# line_kick.net
KiCad netlist of a schematic drawn in EAGLE
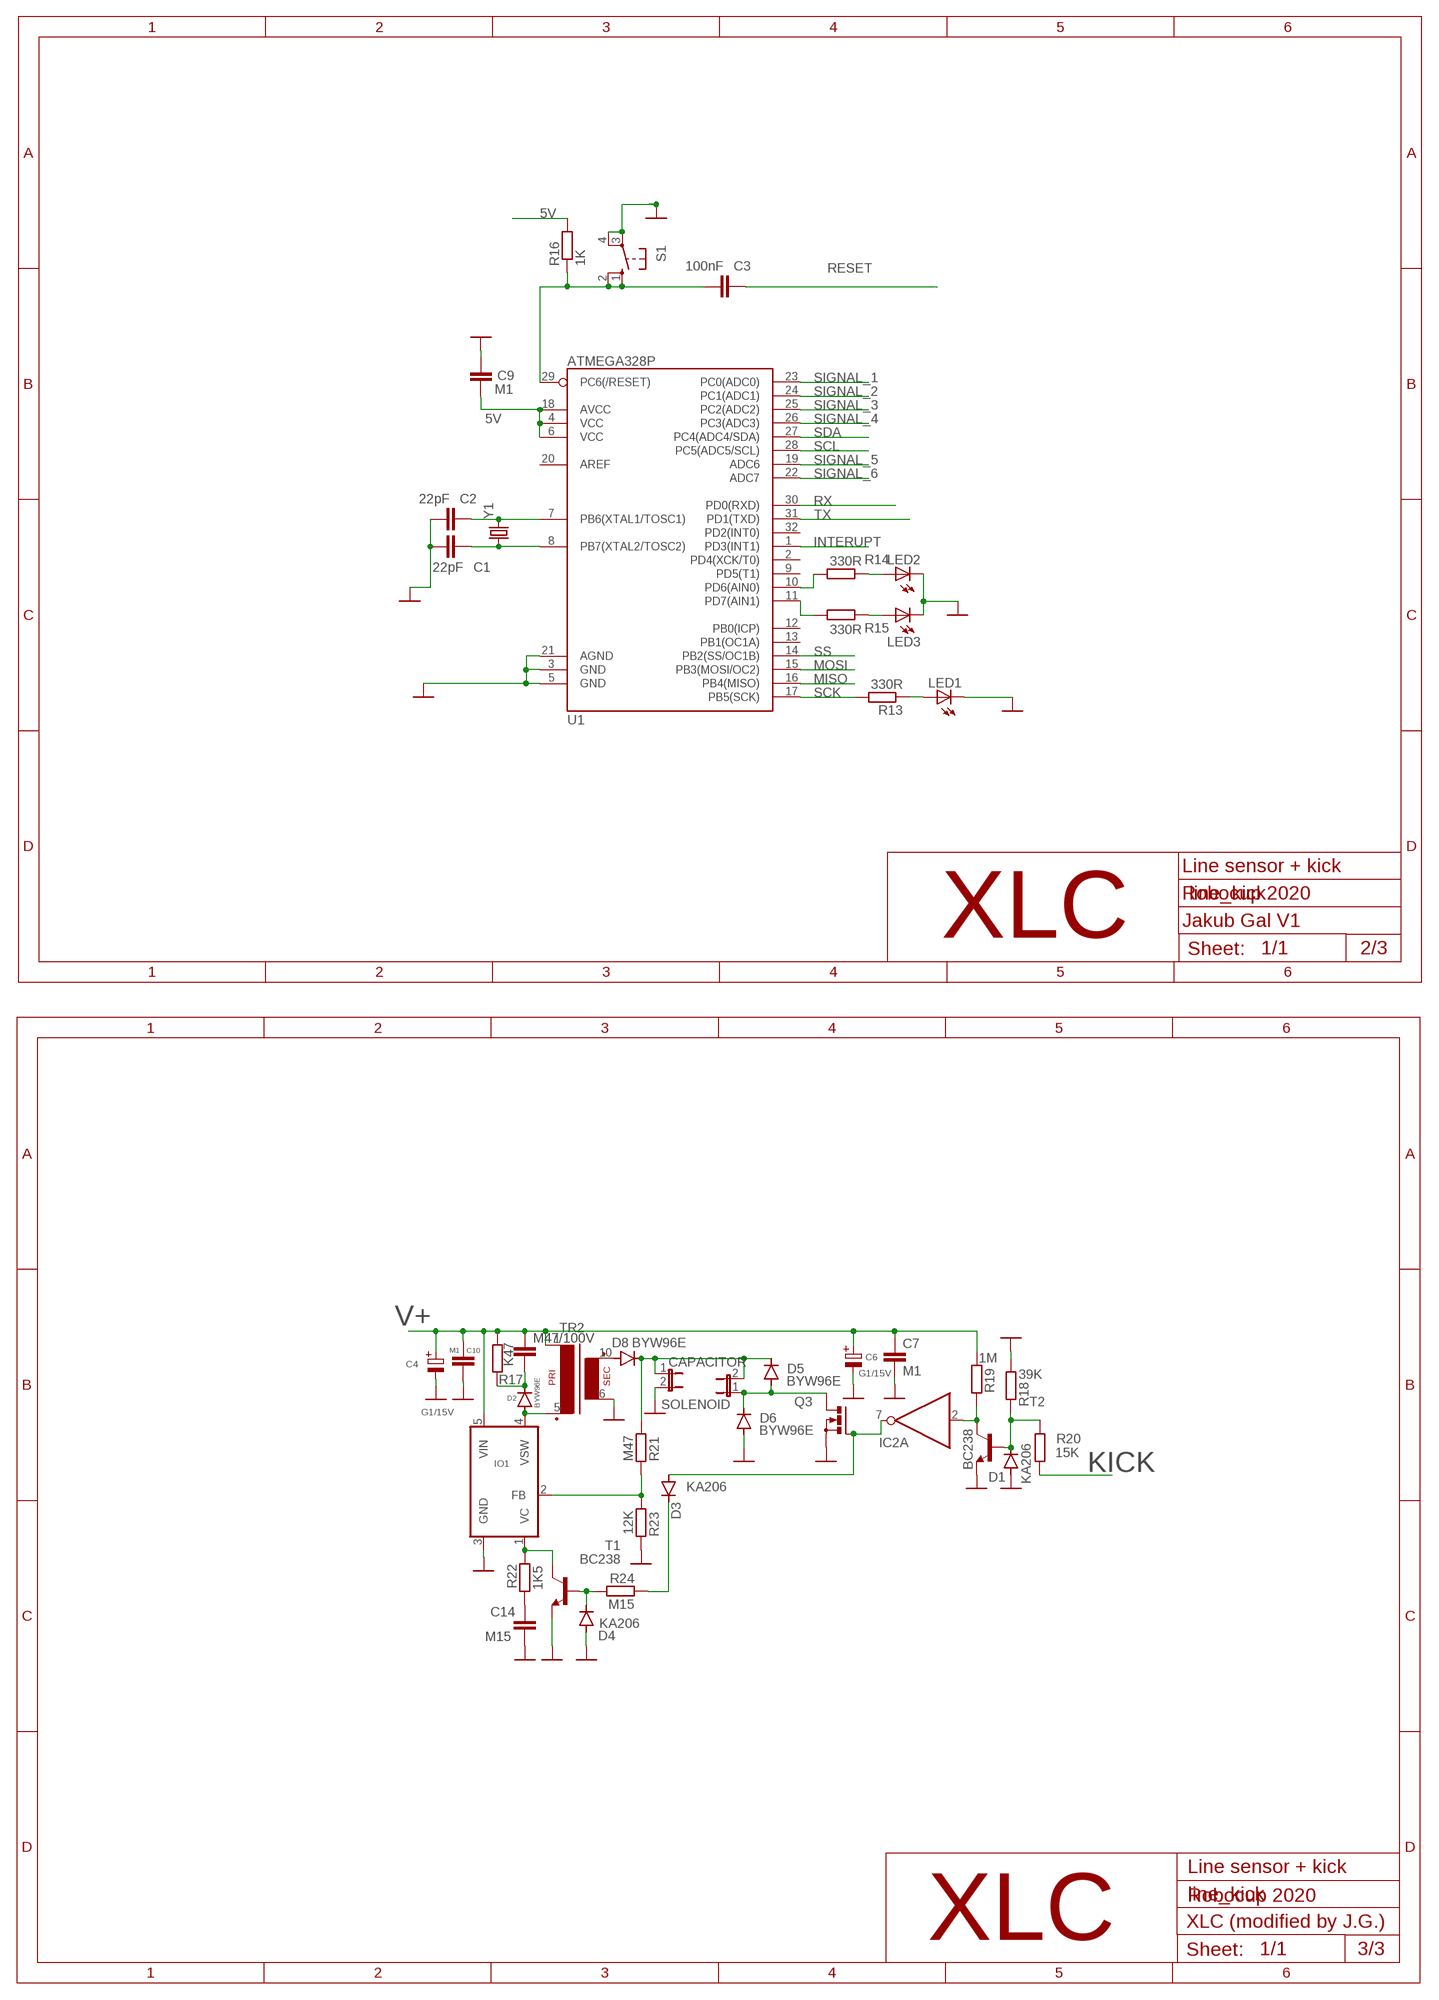
[diagram p0: schematic, sheet 1, part 1 of 2]
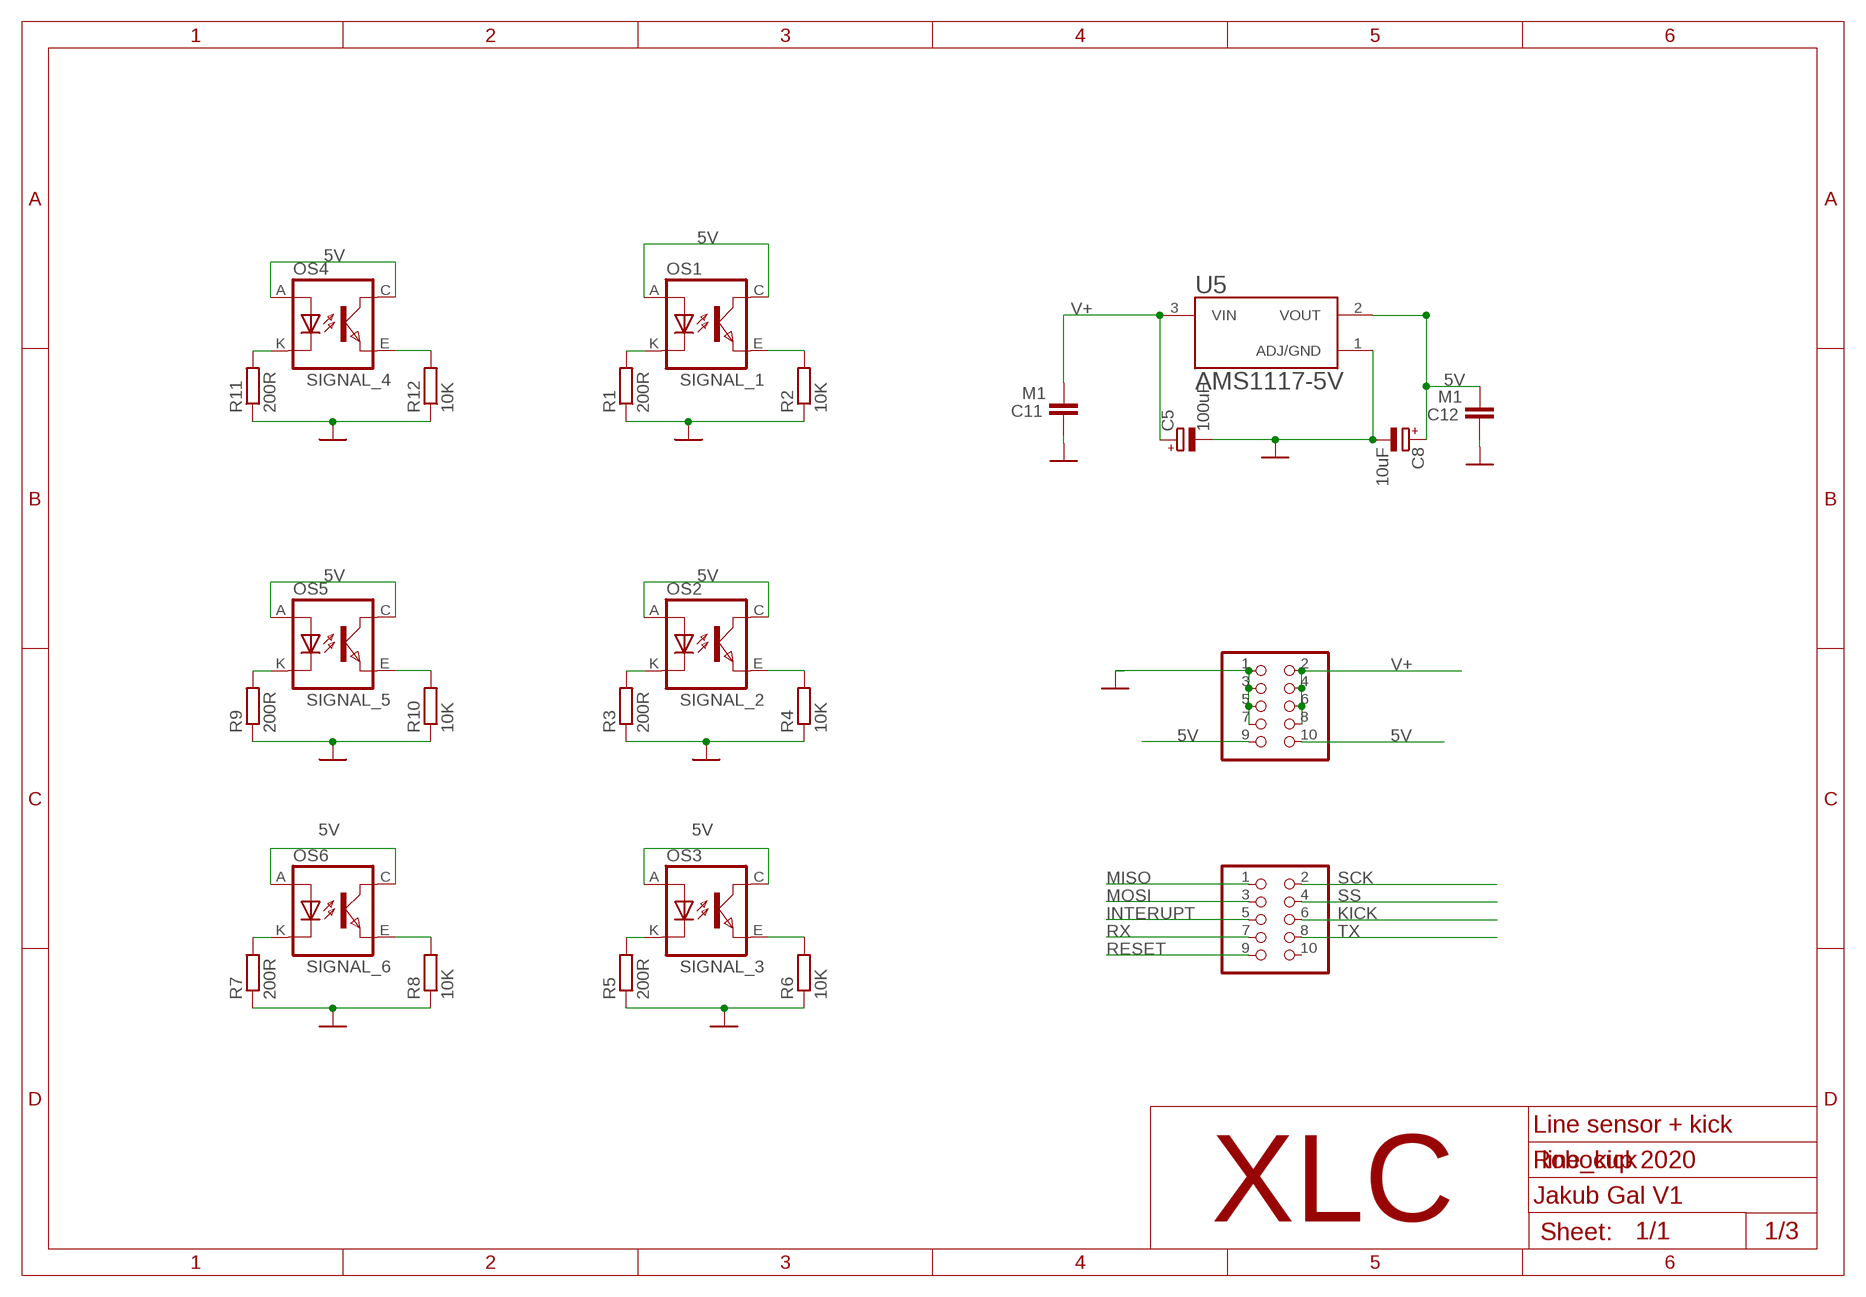
[diagram p1: schematic, sheet 1, part 2 of 2]

(export (version "E")
  (design (tool "Eeschema 10.0.6"))
  (components
    (comp (ref "C1")
      (value "22pF")
      (footprint "eagle-import:C0603")
      (libsource (lib "eagle-import") (part "C-EUC0603"))
    )
    (comp (ref "C2")
      (value "22pF")
      (footprint "eagle-import:C0603")
      (libsource (lib "eagle-import") (part "C-EUC0603"))
    )
    (comp (ref "C3")
      (value "100nF")
      (footprint "eagle-import:C0603")
      (libsource (lib "eagle-import") (part "C-EUC0603"))
    )
    (comp (ref "C4")
      (value "G1/15V")
      (footprint "eagle-import:E-2,5_7-RAD")
      (libsource (lib "eagle-import") (part "KOND-ELEKT-2,5/7"))
    )
    (comp (ref "C5")
      (value "100uF")
      (footprint "eagle-import:UD-6,3X7,7_NICHICON")
      (libsource (lib "eagle-import") (part "CPOL-EUUD-6,3X7,7"))
    )
    (comp (ref "C6")
      (value "G1/15V")
      (footprint "eagle-import:E-2,5_7-RAD")
      (libsource (lib "eagle-import") (part "KOND-ELEKT-2,5/7"))
    )
    (comp (ref "C7")
      (value "M1")
      (footprint "eagle-import:C0805K")
      (libsource (lib "eagle-import") (part "resistor_348_C-EUC0805K"))
    )
    (comp (ref "C8")
      (value "10uF")
      (footprint "eagle-import:UD-4X5,8_NICHICON")
      (libsource (lib "eagle-import") (part "CPOL-EUUD-4X5,8"))
    )
    (comp (ref "C9")
      (value "M1")
      (footprint "eagle-import:C0603")
      (libsource (lib "eagle-import") (part "C-EUC0603"))
    )
    (comp (ref "C10")
      (value "M1")
      (footprint "eagle-import:C0805K")
      (libsource (lib "eagle-import") (part "resistor_348_C-EUC0805K"))
    )
    (comp (ref "C11")
      (value "M1")
      (footprint "eagle-import:C0603")
      (libsource (lib "eagle-import") (part "C-EUC0603"))
    )
    (comp (ref "C12")
      (value "M1")
      (footprint "eagle-import:C0603")
      (libsource (lib "eagle-import") (part "C-EUC0603"))
    )
    (comp (ref "C14")
      (value "M15")
      (footprint "eagle-import:C0805K")
      (libsource (lib "eagle-import") (part "resistor_348_C-EUC0805K"))
    )
    (comp (ref "CAPACITOR")
      (value "JP1E")
      (footprint "eagle-import:JP1")
      (libsource (lib "eagle-import") (part "JP1E"))
    )
    (comp (ref "D1")
      (value "KA206")
      (footprint "eagle-import:D-7.5")
      (libsource (lib "eagle-import") (part "DIODE-D-7.5"))
    )
    (comp (ref "D2")
      (value "BYW96E")
      (footprint "eagle-import:SOD64-10")
      (libsource (lib "eagle-import") (part "BYW96"))
    )
    (comp (ref "D3")
      (value "KA206")
      (footprint "eagle-import:D-7.5")
      (libsource (lib "eagle-import") (part "DIODE-D-7.5"))
    )
    (comp (ref "D4")
      (value "KA206")
      (footprint "eagle-import:D-7.5")
      (libsource (lib "eagle-import") (part "DIODE-D-7.5"))
    )
    (comp (ref "D5")
      (value "BYW96E")
      (footprint "eagle-import:SOD64-10")
      (libsource (lib "eagle-import") (part "BYW96"))
    )
    (comp (ref "D6")
      (value "BYW96E")
      (footprint "eagle-import:SOD64-10")
      (libsource (lib "eagle-import") (part "BYW96"))
    )
    (comp (ref "D8")
      (value "BYW96E")
      (footprint "eagle-import:SOD64-10")
      (libsource (lib "eagle-import") (part "BYW96"))
    )
    (comp (ref "IC2")
      (value "MIC4423BM")
      (footprint "eagle-import:SO08")
      (libsource (lib "eagle-import") (part "MIC4423BM"))
    )
    (comp (ref "IO1")
      (value "LT1071V")
      (footprint "eagle-import:TO220-5P")
      (libsource (lib "eagle-import") (part "LT1071V"))
    )
    (comp (ref "JP2")
      (value "PINHD-2X5")
      (footprint "eagle-import:2X05")
      (libsource (lib "eagle-import") (part "PINHD-2X5"))
    )
    (comp (ref "JP3")
      (value "PINHD-2X5")
      (footprint "eagle-import:2X05")
      (libsource (lib "eagle-import") (part "PINHD-2X5"))
    )
    (comp (ref "LED1")
      (value "LEDCHIPLED_0603")
      (footprint "eagle-import:CHIPLED_0603")
      (libsource (lib "eagle-import") (part "LEDCHIPLED_0603"))
    )
    (comp (ref "LED2")
      (value "LEDCHIPLED_0603")
      (footprint "eagle-import:CHIPLED_0603")
      (libsource (lib "eagle-import") (part "LEDCHIPLED_0603"))
    )
    (comp (ref "LED3")
      (value "LEDCHIPLED_0603")
      (footprint "eagle-import:CHIPLED_0603")
      (libsource (lib "eagle-import") (part "LEDCHIPLED_0603"))
    )
    (comp (ref "M47/100V")
      (value "C-EUC0805K")
      (footprint "eagle-import:C0805K")
      (libsource (lib "eagle-import") (part "resistor_348_C-EUC0805K"))
    )
    (comp (ref "OS1")
      (value "TCRT5000")
      (footprint "eagle-import:TCRT5000")
      (libsource (lib "eagle-import") (part "TCRT5000"))
    )
    (comp (ref "OS2")
      (value "TCRT5000")
      (footprint "eagle-import:TCRT5000")
      (libsource (lib "eagle-import") (part "TCRT5000"))
    )
    (comp (ref "OS3")
      (value "TCRT5000")
      (footprint "eagle-import:TCRT5000")
      (libsource (lib "eagle-import") (part "TCRT5000"))
    )
    (comp (ref "OS4")
      (value "TCRT5000")
      (footprint "eagle-import:TCRT5000")
      (fields (field (name "SPICEPREFIX") "O"))
      (libsource (lib "eagle-import") (part "TCRT5000"))
    )
    (comp (ref "OS5")
      (value "TCRT5000")
      (footprint "eagle-import:TCRT5000")
      (libsource (lib "eagle-import") (part "TCRT5000"))
    )
    (comp (ref "OS6")
      (value "TCRT5000")
      (footprint "eagle-import:TCRT5000")
      (fields (field (name "SPICEPREFIX") "O"))
      (libsource (lib "eagle-import") (part "TCRT5000"))
    )
    (comp (ref "Q3")
      (value "PMOSFET_NTO220BV")
      (footprint "eagle-import:TO220BV")
      (libsource (lib "eagle-import") (part "PMOSFET_NTO220BV"))
    )
    (comp (ref "R1")
      (value "200R")
      (footprint "eagle-import:R0603")
      (libsource (lib "eagle-import") (part "R-EU_R0603"))
    )
    (comp (ref "R2")
      (value "10K")
      (footprint "eagle-import:R0603")
      (libsource (lib "eagle-import") (part "R-EU_R0603"))
    )
    (comp (ref "R3")
      (value "200R")
      (footprint "eagle-import:R0603")
      (libsource (lib "eagle-import") (part "R-EU_R0603"))
    )
    (comp (ref "R4")
      (value "10K")
      (footprint "eagle-import:R0603")
      (libsource (lib "eagle-import") (part "R-EU_R0603"))
    )
    (comp (ref "R5")
      (value "200R")
      (footprint "eagle-import:R0603")
      (libsource (lib "eagle-import") (part "R-EU_R0603"))
    )
    (comp (ref "R6")
      (value "10K")
      (footprint "eagle-import:R0603")
      (libsource (lib "eagle-import") (part "R-EU_R0603"))
    )
    (comp (ref "R7")
      (value "200R")
      (footprint "eagle-import:R0603")
      (libsource (lib "eagle-import") (part "R-EU_R0603"))
    )
    (comp (ref "R8")
      (value "10K")
      (footprint "eagle-import:R0603")
      (libsource (lib "eagle-import") (part "R-EU_R0603"))
    )
    (comp (ref "R9")
      (value "200R")
      (footprint "eagle-import:R0603")
      (libsource (lib "eagle-import") (part "R-EU_R0603"))
    )
    (comp (ref "R10")
      (value "10K")
      (footprint "eagle-import:R0603")
      (libsource (lib "eagle-import") (part "R-EU_R0603"))
    )
    (comp (ref "R11")
      (value "200R")
      (footprint "eagle-import:R0603")
      (libsource (lib "eagle-import") (part "R-EU_R0603"))
    )
    (comp (ref "R12")
      (value "10K")
      (footprint "eagle-import:R0603")
      (libsource (lib "eagle-import") (part "R-EU_R0603"))
    )
    (comp (ref "R13")
      (value "330R")
      (footprint "eagle-import:R0603")
      (libsource (lib "eagle-import") (part "R-EU_R0603"))
    )
    (comp (ref "R14")
      (value "330R")
      (footprint "eagle-import:R0603")
      (libsource (lib "eagle-import") (part "R-EU_R0603"))
    )
    (comp (ref "R15")
      (value "330R")
      (footprint "eagle-import:R0603")
      (libsource (lib "eagle-import") (part "R-EU_R0603"))
    )
    (comp (ref "R16")
      (value "1K")
      (footprint "eagle-import:R0603")
      (libsource (lib "eagle-import") (part "R-EU_R0603"))
    )
    (comp (ref "R17")
      (value "K47")
      (footprint "eagle-import:R0603")
      (libsource (lib "eagle-import") (part "resistor_348_R-EU_R0603"))
    )
    (comp (ref "R18")
      (value "39K")
      (footprint "eagle-import:R0603")
      (libsource (lib "eagle-import") (part "resistor_348_R-EU_R0603"))
    )
    (comp (ref "R19")
      (value "1M")
      (footprint "eagle-import:R0603")
      (libsource (lib "eagle-import") (part "resistor_348_R-EU_R0603"))
    )
    (comp (ref "R20")
      (value "15K")
      (footprint "eagle-import:R0603")
      (libsource (lib "eagle-import") (part "resistor_348_R-EU_R0603"))
    )
    (comp (ref "R21")
      (value "M47")
      (footprint "eagle-import:R0603")
      (libsource (lib "eagle-import") (part "resistor_348_R-EU_R0603"))
    )
    (comp (ref "R22")
      (value "1K5")
      (footprint "eagle-import:R0603")
      (libsource (lib "eagle-import") (part "resistor_348_R-EU_R0603"))
    )
    (comp (ref "R23")
      (value "12K")
      (footprint "eagle-import:R0603")
      (libsource (lib "eagle-import") (part "resistor_348_R-EU_R0603"))
    )
    (comp (ref "R24")
      (value "M15")
      (footprint "eagle-import:R0603")
      (libsource (lib "eagle-import") (part "resistor_348_R-EU_R0603"))
    )
    (comp (ref "S1")
      (value "10-XX")
      (footprint "eagle-import:B3F-10XX")
      (fields (field (name "MPN") "B3F-1000"))
      (libsource (lib "eagle-import") (part "10-XX"))
    )
    (comp (ref "SOLENOID")
      (value "JP1E")
      (footprint "eagle-import:JP1")
      (libsource (lib "eagle-import") (part "JP1E"))
    )
    (comp (ref "T1")
      (value "BC238")
      (footprint "eagle-import:TO92")
      (libsource (lib "eagle-import") (part "BC238"))
    )
    (comp (ref "T2")
      (value "BC238")
      (footprint "eagle-import:TO92")
      (libsource (lib "eagle-import") (part "BC238"))
    )
    (comp (ref "TR2")
      (value "TRAFO-E10-R\"\"")
      (footprint "eagle-import:TRAFO-EE17X20")
      (libsource (lib "eagle-import") (part "TRAFO-E10-R{dblquote}{dblquote}"))
    )
    (comp (ref "U1")
      (value "ATMEGA328P")
      (footprint "eagle-import:TQFP32-08")
      (libsource (lib "eagle-import") (part "ATMEGA328_SMT"))
    )
    (comp (ref "U5")
      (value "AMS1117-5V")
      (footprint "eagle-import:SOT229P700X180-4N")
      (fields (field (name "MF") "Advanced Monolithic Systems") (field (name "MP") "AMS1117-3.3"))
      (libsource (lib "eagle-import") (part "AMS1117-3.3"))
    )
    (comp (ref "Y1")
      (value "CRYSTALHC49US")
      (footprint "eagle-import:HC49US")
      (libsource (lib "eagle-import") (part "CRYSTALHC49US"))
    )
  )
  (nets
    (net (code "1") (name "/5V") (class "Default")
      (node (ref "C12") (pin "1") (pinfunction "1_1") (pintype "passive"))
      (node (ref "C8") (pin "+") (pinfunction "+_+") (pintype "passive"))
      (node (ref "C9") (pin "1") (pinfunction "1_1") (pintype "passive"))
      (node (ref "JP3") (pin "10") (pinfunction "10_10") (pintype "passive"))
      (node (ref "JP3") (pin "9") (pinfunction "9_9") (pintype "passive"))
      (node (ref "OS1") (pin "A") (pinfunction "ANODE_A") (pintype "passive"))
      (node (ref "OS1") (pin "C") (pinfunction "COLLECTOR_C") (pintype "passive"))
      (node (ref "OS2") (pin "A") (pinfunction "ANODE_A") (pintype "passive"))
      (node (ref "OS2") (pin "C") (pinfunction "COLLECTOR_C") (pintype "passive"))
      (node (ref "OS3") (pin "A") (pinfunction "ANODE_A") (pintype "passive"))
      (node (ref "OS3") (pin "C") (pinfunction "COLLECTOR_C") (pintype "passive"))
      (node (ref "OS4") (pin "A") (pinfunction "ANODE_A") (pintype "passive"))
      (node (ref "OS4") (pin "C") (pinfunction "COLLECTOR_C") (pintype "passive"))
      (node (ref "OS5") (pin "A") (pinfunction "ANODE_A") (pintype "passive"))
      (node (ref "OS5") (pin "C") (pinfunction "COLLECTOR_C") (pintype "passive"))
      (node (ref "OS6") (pin "A") (pinfunction "ANODE_A") (pintype "passive"))
      (node (ref "OS6") (pin "C") (pinfunction "COLLECTOR_C") (pintype "passive"))
      (node (ref "R16") (pin "2") (pinfunction "2_2") (pintype "passive"))
      (node (ref "U1") (pin "18") (pinfunction "AVCC_18") (pintype "bidirectional"))
      (node (ref "U1") (pin "4") (pinfunction "VCC_4") (pintype "bidirectional"))
      (node (ref "U1") (pin "6") (pinfunction "VCC_6") (pintype "bidirectional"))
      (node (ref "U5") (pin "2") (pinfunction "VOUT_2") (pintype "output"))
    )
    (net (code "2") (name "/INTERUPT") (class "Default")
      (node (ref "JP2") (pin "5") (pinfunction "5_5") (pintype "passive"))
      (node (ref "U1") (pin "1") (pinfunction "PD3(INT1)_1") (pintype "bidirectional"))
    )
    (net (code "3") (name "/KICK") (class "Default")
      (node (ref "JP2") (pin "6") (pinfunction "6_6") (pintype "passive"))
      (node (ref "R20") (pin "1") (pinfunction "1_1") (pintype "passive"))
    )
    (net (code "4") (name "/MISO") (class "Default")
      (node (ref "JP2") (pin "1") (pinfunction "1_1") (pintype "passive"))
      (node (ref "U1") (pin "16") (pinfunction "PB4(MISO)_16") (pintype "bidirectional"))
    )
    (net (code "5") (name "/MOSI") (class "Default")
      (node (ref "JP2") (pin "3") (pinfunction "3_3") (pintype "passive"))
      (node (ref "U1") (pin "15") (pinfunction "PB3(MOSI/OC2)_15") (pintype "bidirectional"))
    )
    (net (code "6") (name "/RESET") (class "Default")
      (node (ref "C3") (pin "2") (pinfunction "2_2") (pintype "passive"))
      (node (ref "JP2") (pin "9") (pinfunction "9_9") (pintype "passive"))
    )
    (net (code "7") (name "/RX") (class "Default")
      (node (ref "JP2") (pin "7") (pinfunction "7_7") (pintype "passive"))
      (node (ref "U1") (pin "30") (pinfunction "PD0(RXD)_30") (pintype "bidirectional"))
    )
    (net (code "8") (name "/SCK") (class "Default")
      (node (ref "JP2") (pin "2") (pinfunction "2_2") (pintype "passive"))
      (node (ref "R13") (pin "2") (pinfunction "2_2") (pintype "passive"))
      (node (ref "U1") (pin "17") (pinfunction "PB5(SCK)_17") (pintype "bidirectional"))
    )
    (net (code "9") (name "/SCL") (class "Default")
      (node (ref "U1") (pin "28") (pinfunction "PC5(ADC5/SCL)_28") (pintype "bidirectional"))
    )
    (net (code "10") (name "/SDA") (class "Default")
      (node (ref "U1") (pin "27") (pinfunction "PC4(ADC4/SDA)_27") (pintype "bidirectional"))
    )
    (net (code "11") (name "/SIGNAL_1") (class "Default")
      (node (ref "OS1") (pin "E") (pinfunction "EMITTER_E") (pintype "passive"))
      (node (ref "R2") (pin "2") (pinfunction "2_2") (pintype "passive"))
      (node (ref "U1") (pin "23") (pinfunction "PC0(ADC0)_23") (pintype "bidirectional"))
    )
    (net (code "12") (name "/SIGNAL_2") (class "Default")
      (node (ref "OS2") (pin "E") (pinfunction "EMITTER_E") (pintype "passive"))
      (node (ref "R4") (pin "2") (pinfunction "2_2") (pintype "passive"))
      (node (ref "U1") (pin "24") (pinfunction "PC1(ADC1)_24") (pintype "bidirectional"))
    )
    (net (code "13") (name "/SIGNAL_3") (class "Default")
      (node (ref "OS3") (pin "E") (pinfunction "EMITTER_E") (pintype "passive"))
      (node (ref "R6") (pin "2") (pinfunction "2_2") (pintype "passive"))
      (node (ref "U1") (pin "25") (pinfunction "PC2(ADC2)_25") (pintype "bidirectional"))
    )
    (net (code "14") (name "/SIGNAL_4") (class "Default")
      (node (ref "OS4") (pin "E") (pinfunction "EMITTER_E") (pintype "passive"))
      (node (ref "R12") (pin "2") (pinfunction "2_2") (pintype "passive"))
      (node (ref "U1") (pin "26") (pinfunction "PC3(ADC3)_26") (pintype "bidirectional"))
    )
    (net (code "15") (name "/SIGNAL_5") (class "Default")
      (node (ref "OS5") (pin "E") (pinfunction "EMITTER_E") (pintype "passive"))
      (node (ref "R10") (pin "2") (pinfunction "2_2") (pintype "passive"))
      (node (ref "U1") (pin "19") (pinfunction "ADC6_19") (pintype "bidirectional"))
    )
    (net (code "16") (name "/SIGNAL_6") (class "Default")
      (node (ref "OS6") (pin "E") (pinfunction "EMITTER_E") (pintype "passive"))
      (node (ref "R8") (pin "2") (pinfunction "2_2") (pintype "passive"))
      (node (ref "U1") (pin "22") (pinfunction "ADC7_22") (pintype "bidirectional"))
    )
    (net (code "17") (name "/SS") (class "Default")
      (node (ref "JP2") (pin "4") (pinfunction "4_4") (pintype "passive"))
      (node (ref "U1") (pin "14") (pinfunction "PB2(SS/OC1B)_14") (pintype "bidirectional"))
    )
    (net (code "18") (name "/TX") (class "Default")
      (node (ref "JP2") (pin "8") (pinfunction "8_8") (pintype "passive"))
      (node (ref "U1") (pin "31") (pinfunction "PD1(TXD)_31") (pintype "bidirectional"))
    )
    (net (code "19") (name "/V+") (class "Default")
      (node (ref "C10") (pin "1") (pinfunction "1_1") (pintype "passive"))
      (node (ref "C11") (pin "1") (pinfunction "1_1") (pintype "passive"))
      (node (ref "C4") (pin "+") (pinfunction "+_+") (pintype "passive"))
      (node (ref "C5") (pin "+") (pinfunction "+_+") (pintype "passive"))
      (node (ref "C6") (pin "+") (pinfunction "+_+") (pintype "passive"))
      (node (ref "C7") (pin "1") (pinfunction "1_1") (pintype "passive"))
      (node (ref "IO1") (pin "5") (pinfunction "VIN_5") (pintype "power_in"))
      (node (ref "JP3") (pin "2") (pinfunction "2_2") (pintype "passive"))
      (node (ref "JP3") (pin "4") (pinfunction "4_4") (pintype "passive"))
      (node (ref "JP3") (pin "6") (pinfunction "6_6") (pintype "passive"))
      (node (ref "JP3") (pin "8") (pinfunction "8_8") (pintype "passive"))
      (node (ref "M47/100V") (pin "1") (pinfunction "1_1") (pintype "passive"))
      (node (ref "R17") (pin "1") (pinfunction "1_1") (pintype "passive"))
      (node (ref "R19") (pin "2") (pinfunction "2_2") (pintype "passive"))
      (node (ref "TR2") (pin "1") (pinfunction "1_1") (pintype "passive"))
      (node (ref "U5") (pin "3") (pinfunction "VIN_3") (pintype "input"))
    )
    (net (code "20") (name "GND") (class "Default")
      (node (ref "C1") (pin "1") (pinfunction "1_1") (pintype "passive"))
      (node (ref "C10") (pin "2") (pinfunction "2_2") (pintype "passive"))
      (node (ref "C11") (pin "2") (pinfunction "2_2") (pintype "passive"))
      (node (ref "C12") (pin "2") (pinfunction "2_2") (pintype "passive"))
      (node (ref "C14") (pin "2") (pinfunction "2_2") (pintype "passive"))
      (node (ref "C2") (pin "1") (pinfunction "1_1") (pintype "passive"))
      (node (ref "C4") (pin "-") (pinfunction "-_-") (pintype "passive"))
      (node (ref "C5") (pin "-") (pinfunction "-_-") (pintype "passive"))
      (node (ref "C6") (pin "-") (pinfunction "-_-") (pintype "passive"))
      (node (ref "C7") (pin "2") (pinfunction "2_2") (pintype "passive"))
      (node (ref "C8") (pin "-") (pinfunction "-_-") (pintype "passive"))
      (node (ref "C9") (pin "2") (pinfunction "2_2") (pintype "passive"))
      (node (ref "CAPACITOR") (pin "2") (pinfunction "2_2") (pintype "passive"))
      (node (ref "D1") (pin "A") (pinfunction "A_A") (pintype "passive"))
      (node (ref "D4") (pin "A") (pinfunction "A_A") (pintype "passive"))
      (node (ref "D6") (pin "A") (pinfunction "A_A") (pintype "passive"))
      (node (ref "IO1") (pin "3") (pinfunction "GND_3") (pintype "power_in"))
      (node (ref "JP3") (pin "1") (pinfunction "1_1") (pintype "passive"))
      (node (ref "JP3") (pin "3") (pinfunction "3_3") (pintype "passive"))
      (node (ref "JP3") (pin "5") (pinfunction "5_5") (pintype "passive"))
      (node (ref "JP3") (pin "7") (pinfunction "7_7") (pintype "passive"))
      (node (ref "LED1") (pin "C") (pinfunction "C_C") (pintype "passive"))
      (node (ref "LED2") (pin "C") (pinfunction "C_C") (pintype "passive"))
      (node (ref "LED3") (pin "C") (pinfunction "C_C") (pintype "passive"))
      (node (ref "Q3") (pin "S") (pinfunction "S_S") (pintype "passive"))
      (node (ref "R1") (pin "1") (pinfunction "1_1") (pintype "passive"))
      (node (ref "R10") (pin "1") (pinfunction "1_1") (pintype "passive"))
      (node (ref "R11") (pin "1") (pinfunction "1_1") (pintype "passive"))
      (node (ref "R12") (pin "1") (pinfunction "1_1") (pintype "passive"))
      (node (ref "R18") (pin "2") (pinfunction "2_2") (pintype "passive"))
      (node (ref "R2") (pin "1") (pinfunction "1_1") (pintype "passive"))
      (node (ref "R23") (pin "1") (pinfunction "1_1") (pintype "passive"))
      (node (ref "R3") (pin "1") (pinfunction "1_1") (pintype "passive"))
      (node (ref "R4") (pin "1") (pinfunction "1_1") (pintype "passive"))
      (node (ref "R5") (pin "1") (pinfunction "1_1") (pintype "passive"))
      (node (ref "R6") (pin "1") (pinfunction "1_1") (pintype "passive"))
      (node (ref "R7") (pin "1") (pinfunction "1_1") (pintype "passive"))
      (node (ref "R8") (pin "1") (pinfunction "1_1") (pintype "passive"))
      (node (ref "R9") (pin "1") (pinfunction "1_1") (pintype "passive"))
      (node (ref "S1") (pin "3") (pinfunction "P_3") (pintype "passive"))
      (node (ref "S1") (pin "4") (pinfunction "P1_4") (pintype "passive"))
      (node (ref "T1") (pin "1") (pinfunction "E_1") (pintype "passive"))
      (node (ref "T2") (pin "1") (pinfunction "E_1") (pintype "passive"))
      (node (ref "TR2") (pin "6") (pinfunction "3_6") (pintype "passive"))
      (node (ref "U1") (pin "21") (pinfunction "AGND_21") (pintype "bidirectional"))
      (node (ref "U1") (pin "3") (pinfunction "GND_3") (pintype "bidirectional"))
      (node (ref "U1") (pin "5") (pinfunction "GND_5") (pintype "bidirectional"))
      (node (ref "U5") (pin "1") (pinfunction "ADJ/GND_1") (pintype "power_in"))
    )
    (net (code "21") (name "Net-(C14-Pad1)") (class "Default")
      (node (ref "C14") (pin "1") (pinfunction "1_1") (pintype "passive"))
      (node (ref "R22") (pin "2") (pinfunction "2_2") (pintype "passive"))
    )
    (net (code "22") (name "Net-(CAPACITOR-Pad1)") (class "Default")
      (node (ref "CAPACITOR") (pin "1") (pinfunction "1_1") (pintype "passive"))
      (node (ref "D5") (pin "C") (pinfunction "C_C") (pintype "passive"))
      (node (ref "D8") (pin "C") (pinfunction "C_C") (pintype "passive"))
      (node (ref "R21") (pin "2") (pinfunction "2_2") (pintype "passive"))
      (node (ref "SOLENOID") (pin "2") (pinfunction "2_2") (pintype "passive"))
    )
    (net (code "23") (name "Net-(D2-PadC)") (class "Default")
      (node (ref "D2") (pin "C") (pinfunction "C_C") (pintype "passive"))
      (node (ref "M47/100V") (pin "2") (pinfunction "2_2") (pintype "passive"))
      (node (ref "R17") (pin "2") (pinfunction "2_2") (pintype "passive"))
    )
    (net (code "24") (name "Net-(D3-PadC)") (class "Default")
      (node (ref "D3") (pin "C") (pinfunction "C_C") (pintype "passive"))
      (node (ref "R24") (pin "1") (pinfunction "1_1") (pintype "passive"))
    )
    (net (code "25") (name "Net-(D5-PadA)") (class "Default")
      (node (ref "D5") (pin "A") (pinfunction "A_A") (pintype "passive"))
      (node (ref "D6") (pin "C") (pinfunction "C_C") (pintype "passive"))
      (node (ref "Q3") (pin "D") (pinfunction "D_D") (pintype "passive"))
      (node (ref "SOLENOID") (pin "1") (pinfunction "1_1") (pintype "passive"))
    )
    (net (code "26") (name "Net-(IC2A-IN)") (class "Default")
      (node (ref "IC2") (pin "2") (pinfunction "IN_2") (pintype "input"))
      (node (ref "R19") (pin "1") (pinfunction "1_1") (pintype "passive"))
      (node (ref "T2") (pin "3") (pinfunction "C_3") (pintype "passive"))
    )
    (net (code "27") (name "Net-(IC2A-OUT)") (class "Default")
      (node (ref "D3") (pin "A") (pinfunction "A_A") (pintype "passive"))
      (node (ref "IC2") (pin "7") (pinfunction "OUT_7") (pintype "output"))
      (node (ref "Q3") (pin "G") (pinfunction "G_G") (pintype "passive"))
    )
    (net (code "28") (name "Net-(IO1-FB)") (class "Default")
      (node (ref "IO1") (pin "2") (pinfunction "FB_2") (pintype "input"))
      (node (ref "R21") (pin "1") (pinfunction "1_1") (pintype "passive"))
      (node (ref "R23") (pin "2") (pinfunction "2_2") (pintype "passive"))
    )
    (net (code "29") (name "Net-(IO1-VC)") (class "Default")
      (node (ref "IO1") (pin "1") (pinfunction "VC_1") (pintype "input"))
      (node (ref "R22") (pin "1") (pinfunction "1_1") (pintype "passive"))
      (node (ref "T1") (pin "3") (pinfunction "C_3") (pintype "passive"))
    )
    (net (code "30") (name "Net-(IO1-VSW)") (class "Default")
      (node (ref "D2") (pin "A") (pinfunction "A_A") (pintype "passive"))
      (node (ref "IO1") (pin "4") (pinfunction "VSW_4") (pintype "output"))
      (node (ref "TR2") (pin "5") (pinfunction "2_5") (pintype "passive"))
    )
    (net (code "31") (name "Net-(LED1-PadA)") (class "Default")
      (node (ref "LED1") (pin "A") (pinfunction "A_A") (pintype "passive"))
      (node (ref "R13") (pin "1") (pinfunction "1_1") (pintype "passive"))
    )
    (net (code "32") (name "Net-(LED2-PadA)") (class "Default")
      (node (ref "LED2") (pin "A") (pinfunction "A_A") (pintype "passive"))
      (node (ref "R14") (pin "1") (pinfunction "1_1") (pintype "passive"))
    )
    (net (code "33") (name "Net-(LED3-PadA)") (class "Default")
      (node (ref "LED3") (pin "A") (pinfunction "A_A") (pintype "passive"))
      (node (ref "R15") (pin "1") (pinfunction "1_1") (pintype "passive"))
    )
    (net (code "34") (name "Net-(OS1-CATHODE)") (class "Default")
      (node (ref "OS1") (pin "K") (pinfunction "CATHODE_K") (pintype "passive"))
      (node (ref "R1") (pin "2") (pinfunction "2_2") (pintype "passive"))
    )
    (net (code "35") (name "Net-(OS2-CATHODE)") (class "Default")
      (node (ref "OS2") (pin "K") (pinfunction "CATHODE_K") (pintype "passive"))
      (node (ref "R3") (pin "2") (pinfunction "2_2") (pintype "passive"))
    )
    (net (code "36") (name "Net-(OS3-CATHODE)") (class "Default")
      (node (ref "OS3") (pin "K") (pinfunction "CATHODE_K") (pintype "passive"))
      (node (ref "R5") (pin "2") (pinfunction "2_2") (pintype "passive"))
    )
    (net (code "37") (name "Net-(OS4-CATHODE)") (class "Default")
      (node (ref "OS4") (pin "K") (pinfunction "CATHODE_K") (pintype "passive"))
      (node (ref "R11") (pin "2") (pinfunction "2_2") (pintype "passive"))
    )
    (net (code "38") (name "Net-(OS5-CATHODE)") (class "Default")
      (node (ref "OS5") (pin "K") (pinfunction "CATHODE_K") (pintype "passive"))
      (node (ref "R9") (pin "2") (pinfunction "2_2") (pintype "passive"))
    )
    (net (code "39") (name "Net-(OS6-CATHODE)") (class "Default")
      (node (ref "OS6") (pin "K") (pinfunction "CATHODE_K") (pintype "passive"))
      (node (ref "R7") (pin "2") (pinfunction "2_2") (pintype "passive"))
    )
    (net (code "40") (name "Net-(S1-S)") (class "Default")
      (node (ref "C3") (pin "1") (pinfunction "1_1") (pintype "passive"))
      (node (ref "R16") (pin "1") (pinfunction "1_1") (pintype "passive"))
      (node (ref "S1") (pin "1") (pinfunction "S_1") (pintype "passive"))
      (node (ref "S1") (pin "2") (pinfunction "S1_2") (pintype "passive"))
      (node (ref "U1") (pin "29") (pinfunction "PC6(/RESET)_29") (pintype "bidirectional"))
    )
    (net (code "41") (name "Net-(T1-B)") (class "Default")
      (node (ref "D4") (pin "C") (pinfunction "C_C") (pintype "passive"))
      (node (ref "R24") (pin "2") (pinfunction "2_2") (pintype "passive"))
      (node (ref "T1") (pin "2") (pinfunction "B_2") (pintype "passive"))
    )
    (net (code "42") (name "Net-(T2-B)") (class "Default")
      (node (ref "D1") (pin "C") (pinfunction "C_C") (pintype "passive"))
      (node (ref "R18") (pin "1") (pinfunction "1_1") (pintype "passive"))
      (node (ref "R20") (pin "2") (pinfunction "2_2") (pintype "passive"))
      (node (ref "T2") (pin "2") (pinfunction "B_2") (pintype "passive"))
    )
    (net (code "43") (name "Net-(TR2-4)") (class "Default")
      (node (ref "D8") (pin "A") (pinfunction "A_A") (pintype "passive"))
      (node (ref "TR2") (pin "10") (pinfunction "4_10") (pintype "passive"))
    )
    (net (code "44") (name "Net-(U1-PB6(XTAL1{slash}TOSC1))") (class "Default")
      (node (ref "C2") (pin "2") (pinfunction "2_2") (pintype "passive"))
      (node (ref "U1") (pin "7") (pinfunction "PB6(XTAL1/TOSC1)_7") (pintype "bidirectional"))
      (node (ref "Y1") (pin "2") (pinfunction "2_2") (pintype "passive"))
    )
    (net (code "45") (name "Net-(U1-PB7(XTAL2{slash}TOSC2))") (class "Default")
      (node (ref "C1") (pin "2") (pinfunction "2_2") (pintype "passive"))
      (node (ref "U1") (pin "8") (pinfunction "PB7(XTAL2/TOSC2)_8") (pintype "bidirectional"))
      (node (ref "Y1") (pin "1") (pinfunction "1_1") (pintype "passive"))
    )
    (net (code "46") (name "Net-(U1-PD6(AIN0))") (class "Default")
      (node (ref "R14") (pin "2") (pinfunction "2_2") (pintype "passive"))
      (node (ref "U1") (pin "10") (pinfunction "PD6(AIN0)_10") (pintype "bidirectional"))
    )
    (net (code "47") (name "Net-(U1-PD7(AIN1))") (class "Default")
      (node (ref "R15") (pin "2") (pinfunction "2_2") (pintype "passive"))
      (node (ref "U1") (pin "11") (pinfunction "PD7(AIN1)_11") (pintype "bidirectional"))
    )
    (net (code "48") (name "unconnected-(JP2-Pad10)") (class "Default")
      (node (ref "JP2") (pin "10") (pinfunction "10_10") (pintype "passive"))
    )
    (net (code "49") (name "unconnected-(U1-AREF-Pad20)") (class "Default")
      (node (ref "U1") (pin "20") (pinfunction "AREF_20") (pintype "bidirectional"))
    )
    (net (code "50") (name "unconnected-(U1-PB0(ICP)-Pad12)") (class "Default")
      (node (ref "U1") (pin "12") (pinfunction "PB0(ICP)_12") (pintype "bidirectional"))
    )
    (net (code "51") (name "unconnected-(U1-PB1(OC1A)-Pad13)") (class "Default")
      (node (ref "U1") (pin "13") (pinfunction "PB1(OC1A)_13") (pintype "bidirectional"))
    )
    (net (code "52") (name "unconnected-(U1-PD2(INT0)-Pad32)") (class "Default")
      (node (ref "U1") (pin "32") (pinfunction "PD2(INT0)_32") (pintype "bidirectional"))
    )
    (net (code "53") (name "unconnected-(U1-PD4(XCK{slash}T0)-Pad2)") (class "Default")
      (node (ref "U1") (pin "2") (pinfunction "PD4(XCK/T0)_2") (pintype "bidirectional"))
    )
    (net (code "54") (name "unconnected-(U1-PD5(T1)-Pad9)") (class "Default")
      (node (ref "U1") (pin "9") (pinfunction "PD5(T1)_9") (pintype "bidirectional"))
    )
  )
)
